# M7672X.net
KiCad netlist of a schematic drawn in EAGLE
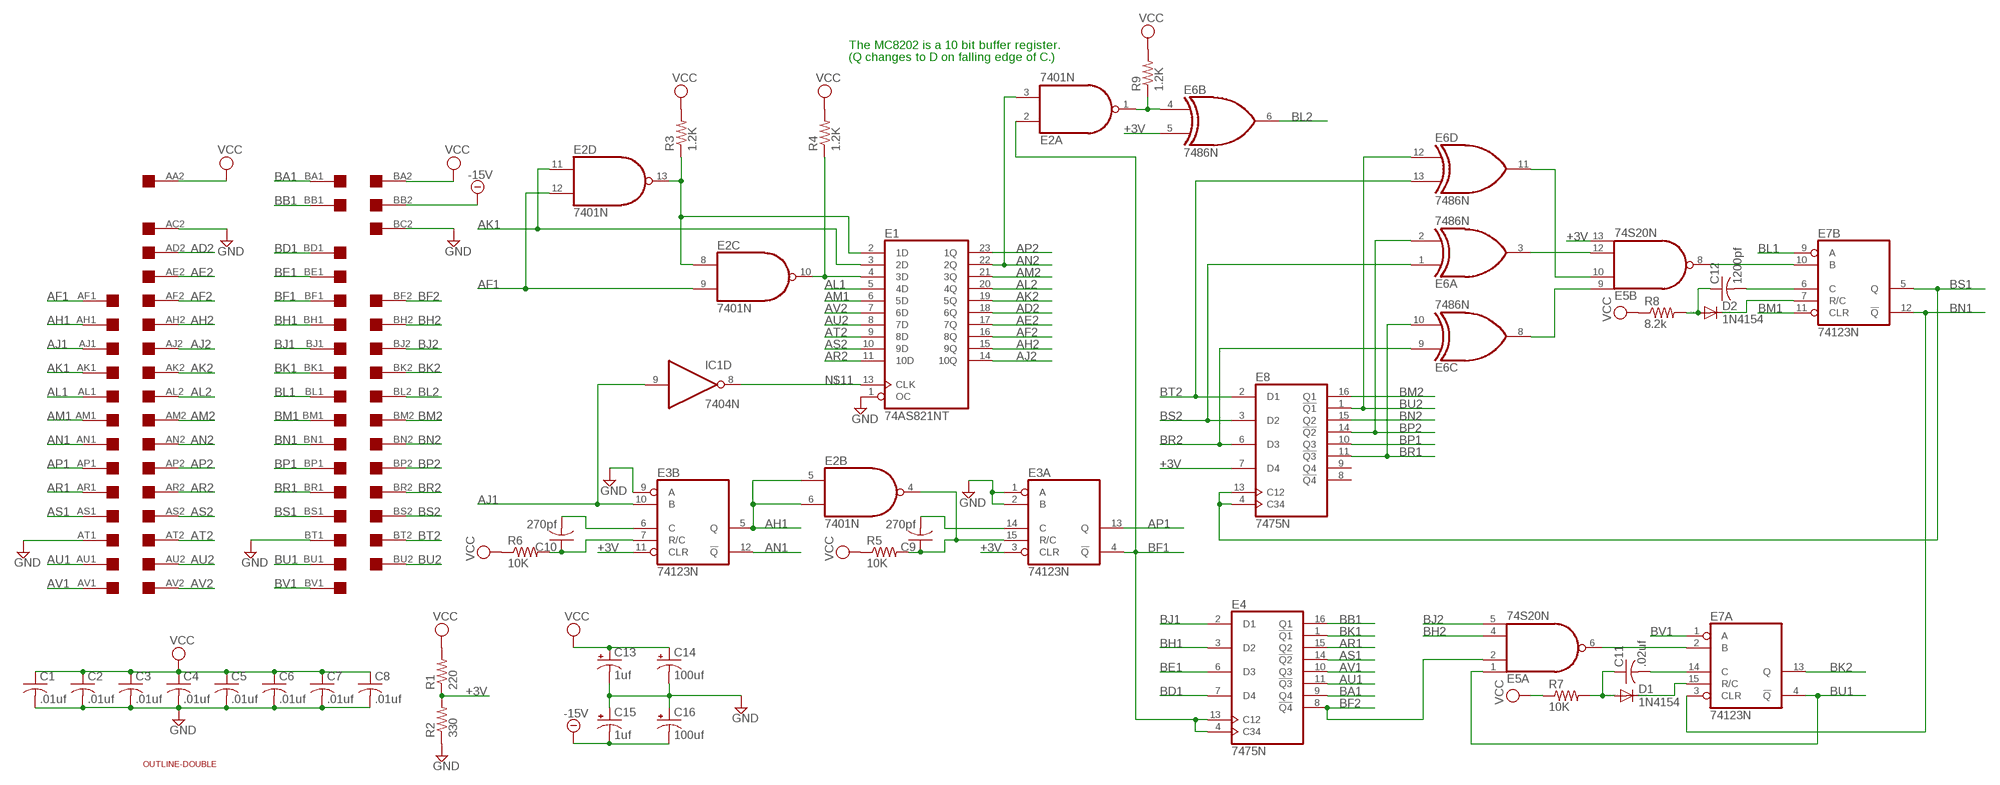
[diagram p0: schematic, sheet 1]

(export (version "E")
  (design (tool "Eeschema 10.0.6"))
  (components
    (comp (ref "C1")
      (value ".01uf")
      (footprint "eagle-import:C050-025X075")
      (libsource (lib "eagle-import") (part "C-US050-025X075"))
    )
    (comp (ref "C2")
      (value ".01uf")
      (footprint "eagle-import:C050-025X075")
      (libsource (lib "eagle-import") (part "C-US050-025X075"))
    )
    (comp (ref "C3")
      (value ".01uf")
      (footprint "eagle-import:C050-025X075")
      (libsource (lib "eagle-import") (part "C-US050-025X075"))
    )
    (comp (ref "C4")
      (value ".01uf")
      (footprint "eagle-import:C050-025X075")
      (libsource (lib "eagle-import") (part "C-US050-025X075"))
    )
    (comp (ref "C5")
      (value ".01uf")
      (footprint "eagle-import:C050-025X075")
      (libsource (lib "eagle-import") (part "C-US050-025X075"))
    )
    (comp (ref "C6")
      (value ".01uf")
      (footprint "eagle-import:C050-025X075")
      (libsource (lib "eagle-import") (part "C-US050-025X075"))
    )
    (comp (ref "C7")
      (value ".01uf")
      (footprint "eagle-import:C050-025X075")
      (libsource (lib "eagle-import") (part "C-US050-025X075"))
    )
    (comp (ref "C8")
      (value ".01uf")
      (footprint "eagle-import:C050-025X075")
      (libsource (lib "eagle-import") (part "C-US050-025X075"))
    )
    (comp (ref "C9")
      (value "270pf")
      (footprint "eagle-import:C050-025X075")
      (libsource (lib "eagle-import") (part "C-US050-025X075"))
    )
    (comp (ref "C10")
      (value "270pf")
      (footprint "eagle-import:C050-025X075")
      (libsource (lib "eagle-import") (part "C-US050-025X075"))
    )
    (comp (ref "C11")
      (value ".02uf")
      (footprint "eagle-import:C050-025X075")
      (libsource (lib "eagle-import") (part "C-US050-025X075"))
    )
    (comp (ref "C12")
      (value "1200pf")
      (footprint "eagle-import:C050-025X075")
      (libsource (lib "eagle-import") (part "C-US050-025X075"))
    )
    (comp (ref "C13")
      (value "1uf")
      (footprint "eagle-import:E30-10")
      (libsource (lib "eagle-import") (part "CPOL-USE30-10AXIAL"))
    )
    (comp (ref "C14")
      (value "100uf")
      (footprint "eagle-import:E30-10")
      (libsource (lib "eagle-import") (part "CPOL-USE30-10AXIAL"))
    )
    (comp (ref "C15")
      (value "1uf")
      (footprint "eagle-import:E30-10")
      (libsource (lib "eagle-import") (part "CPOL-USE30-10AXIAL"))
    )
    (comp (ref "C16")
      (value "100uf")
      (footprint "eagle-import:E30-10")
      (libsource (lib "eagle-import") (part "CPOL-USE30-10AXIAL"))
    )
    (comp (ref "D1")
      (value "1N4154")
      (footprint "eagle-import:DO35-10")
      (libsource (lib "eagle-import") (part "1N4148DO35-10"))
    )
    (comp (ref "D2")
      (value "1N4154")
      (footprint "eagle-import:DO35-10")
      (libsource (lib "eagle-import") (part "1N4148DO35-10"))
    )
    (comp (ref "E1")
      (value "74AS821NT")
      (footprint "eagle-import:DIL24-6")
      (libsource (lib "eagle-import") (part "74821NTAS"))
    )
    (comp (ref "E2")
      (value "7401N")
      (footprint "eagle-import:DIL14")
      (libsource (lib "eagle-import") (part "7401NLS"))
    )
    (comp (ref "E3")
      (value "74123N")
      (footprint "eagle-import:DIL16")
      (libsource (lib "eagle-import") (part "74123N"))
    )
    (comp (ref "E4")
      (value "7475N")
      (footprint "eagle-import:DIL16")
      (libsource (lib "eagle-import") (part "7475N"))
    )
    (comp (ref "E5")
      (value "74S20N")
      (footprint "eagle-import:DIL14")
      (libsource (lib "eagle-import") (part "7420NS"))
    )
    (comp (ref "E6")
      (value "7486N")
      (footprint "eagle-import:DIL14")
      (libsource (lib "eagle-import") (part "7486N"))
    )
    (comp (ref "E7")
      (value "74123N")
      (footprint "eagle-import:DIL16")
      (libsource (lib "eagle-import") (part "74123N"))
    )
    (comp (ref "E8")
      (value "7475N")
      (footprint "eagle-import:DIL16")
      (libsource (lib "eagle-import") (part "7475N"))
    )
    (comp (ref "EDGE")
      (value "DOUBLE")
      (footprint "eagle-import:EDGE-CON4")
      (libsource (lib "eagle-import") (part "DOUBLE"))
    )
    (comp (ref "IC1")
      (value "7404N")
      (footprint "eagle-import:DIL14")
      (libsource (lib "eagle-import") (part "7404N"))
    )
    (comp (ref "R1")
      (value "220")
      (footprint "eagle-import:0207_10")
      (libsource (lib "eagle-import") (part "R-US_0207/10"))
    )
    (comp (ref "R2")
      (value "330")
      (footprint "eagle-import:0207_10")
      (libsource (lib "eagle-import") (part "R-US_0207/10"))
    )
    (comp (ref "R3")
      (value "1.2K")
      (footprint "eagle-import:0207_10")
      (libsource (lib "eagle-import") (part "R-US_0207/10"))
    )
    (comp (ref "R4")
      (value "1.2K")
      (footprint "eagle-import:0207_10")
      (libsource (lib "eagle-import") (part "R-US_0207/10"))
    )
    (comp (ref "R5")
      (value "10K")
      (footprint "eagle-import:0207_10")
      (libsource (lib "eagle-import") (part "R-US_0207/10"))
    )
    (comp (ref "R6")
      (value "10K")
      (footprint "eagle-import:0207_10")
      (libsource (lib "eagle-import") (part "R-US_0207/10"))
    )
    (comp (ref "R7")
      (value "10K")
      (footprint "eagle-import:0207_10")
      (libsource (lib "eagle-import") (part "R-US_0207/10"))
    )
    (comp (ref "R8")
      (value "8.2k")
      (footprint "eagle-import:0207_10")
      (libsource (lib "eagle-import") (part "R-US_0207/10"))
    )
    (comp (ref "R9")
      (value "1.2K")
      (footprint "eagle-import:0207_10")
      (libsource (lib "eagle-import") (part "R-US_0207/10"))
    )
    (comp (ref "U$2")
      (value "OUTLINE-DOUBLE")
      (footprint "eagle-import:DOUBLE")
      (libsource (lib "eagle-import") (part "OUTLINE-DOUBLE"))
    )
  )
  (nets
    (net (code "1") (name "-15V") (class "Default")
      (node (ref "C15") (pin "-") (pinfunction "-_-") (pintype "passive"))
      (node (ref "C16") (pin "-") (pinfunction "-_-") (pintype "passive"))
      (node (ref "EDGE") (pin "BB2") (pinfunction "1_BB2") (pintype "bidirectional"))
    )
    (net (code "2") (name "/+3V") (class "Default")
      (node (ref "E3") (pin "11") (pinfunction "CLR_11") (pintype "input"))
      (node (ref "E3") (pin "3") (pinfunction "CLR_3") (pintype "input"))
      (node (ref "E5") (pin "13") (pinfunction "I3_13") (pintype "input"))
      (node (ref "E6") (pin "5") (pinfunction "I1_5") (pintype "input"))
      (node (ref "E8") (pin "7") (pinfunction "D4_7") (pintype "input"))
      (node (ref "R1") (pin "1") (pinfunction "1_1") (pintype "passive"))
      (node (ref "R2") (pin "2") (pinfunction "2_2") (pintype "passive"))
    )
    (net (code "3") (name "/AD2") (class "Default")
      (node (ref "E1") (pin "18") (pinfunction "6Q_18") (pintype "tri_state"))
      (node (ref "EDGE") (pin "AD2") (pinfunction "1_AD2") (pintype "bidirectional"))
    )
    (net (code "4") (name "/AE2") (class "Default")
      (node (ref "E1") (pin "17") (pinfunction "7Q_17") (pintype "tri_state"))
      (node (ref "EDGE") (pin "AE2") (pinfunction "1_AE2") (pintype "bidirectional"))
    )
    (net (code "5") (name "/AF1") (class "Default")
      (node (ref "E2") (pin "12") (pinfunction "I1_12") (pintype "input"))
      (node (ref "E2") (pin "9") (pinfunction "I1_9") (pintype "input"))
      (node (ref "EDGE") (pin "AF1") (pinfunction "1_AF1") (pintype "bidirectional"))
    )
    (net (code "6") (name "/AF2") (class "Default")
      (node (ref "E1") (pin "16") (pinfunction "8Q_16") (pintype "tri_state"))
      (node (ref "EDGE") (pin "AF2") (pinfunction "1_AF2") (pintype "bidirectional"))
    )
    (net (code "7") (name "/AH1") (class "Default")
      (node (ref "E2") (pin "5") (pinfunction "I0_5") (pintype "input"))
      (node (ref "E2") (pin "6") (pinfunction "I1_6") (pintype "input"))
      (node (ref "E3") (pin "5") (pinfunction "Q_5") (pintype "output"))
      (node (ref "EDGE") (pin "AH1") (pinfunction "1_AH1") (pintype "bidirectional"))
    )
    (net (code "8") (name "/AH2") (class "Default")
      (node (ref "E1") (pin "15") (pinfunction "9Q_15") (pintype "tri_state"))
      (node (ref "EDGE") (pin "AH2") (pinfunction "1_AH2") (pintype "bidirectional"))
    )
    (net (code "9") (name "/AJ1") (class "Default")
      (node (ref "E3") (pin "10") (pinfunction "B_10") (pintype "input"))
      (node (ref "EDGE") (pin "AJ1") (pinfunction "1_AJ1") (pintype "bidirectional"))
      (node (ref "IC1") (pin "9") (pinfunction "I_9") (pintype "input"))
    )
    (net (code "10") (name "/AJ2") (class "Default")
      (node (ref "E1") (pin "14") (pinfunction "10Q_14") (pintype "tri_state"))
      (node (ref "EDGE") (pin "AJ2") (pinfunction "1_AJ2") (pintype "bidirectional"))
    )
    (net (code "11") (name "/AK1") (class "Default")
      (node (ref "E1") (pin "3") (pinfunction "2D_3") (pintype "input"))
      (node (ref "E2") (pin "11") (pinfunction "I0_11") (pintype "input"))
      (node (ref "EDGE") (pin "AK1") (pinfunction "1_AK1") (pintype "bidirectional"))
    )
    (net (code "12") (name "/AK2") (class "Default")
      (node (ref "E1") (pin "19") (pinfunction "5Q_19") (pintype "tri_state"))
      (node (ref "EDGE") (pin "AK2") (pinfunction "1_AK2") (pintype "bidirectional"))
    )
    (net (code "13") (name "/AL1") (class "Default")
      (node (ref "E1") (pin "5") (pinfunction "4D_5") (pintype "input"))
      (node (ref "EDGE") (pin "AL1") (pinfunction "1_AL1") (pintype "bidirectional"))
    )
    (net (code "14") (name "/AL2") (class "Default")
      (node (ref "E1") (pin "20") (pinfunction "4Q_20") (pintype "tri_state"))
      (node (ref "EDGE") (pin "AL2") (pinfunction "1_AL2") (pintype "bidirectional"))
    )
    (net (code "15") (name "/AM1") (class "Default")
      (node (ref "E1") (pin "6") (pinfunction "5D_6") (pintype "input"))
      (node (ref "EDGE") (pin "AM1") (pinfunction "1_AM1") (pintype "bidirectional"))
    )
    (net (code "16") (name "/AM2") (class "Default")
      (node (ref "E1") (pin "21") (pinfunction "3Q_21") (pintype "tri_state"))
      (node (ref "EDGE") (pin "AM2") (pinfunction "1_AM2") (pintype "bidirectional"))
    )
    (net (code "17") (name "/AN1") (class "Default")
      (node (ref "E3") (pin "12") (pinfunction "~{Q}_12") (pintype "output"))
      (node (ref "EDGE") (pin "AN1") (pinfunction "1_AN1") (pintype "bidirectional"))
    )
    (net (code "18") (name "/AN2") (class "Default")
      (node (ref "E1") (pin "22") (pinfunction "2Q_22") (pintype "tri_state"))
      (node (ref "E2") (pin "3") (pinfunction "I1_3") (pintype "input"))
      (node (ref "EDGE") (pin "AN2") (pinfunction "1_AN2") (pintype "bidirectional"))
    )
    (net (code "19") (name "/AP1") (class "Default")
      (node (ref "E3") (pin "13") (pinfunction "Q_13") (pintype "output"))
      (node (ref "EDGE") (pin "AP1") (pinfunction "1_AP1") (pintype "bidirectional"))
    )
    (net (code "20") (name "/AP2") (class "Default")
      (node (ref "E1") (pin "23") (pinfunction "1Q_23") (pintype "tri_state"))
      (node (ref "EDGE") (pin "AP2") (pinfunction "1_AP2") (pintype "bidirectional"))
    )
    (net (code "21") (name "/AR1") (class "Default")
      (node (ref "E4") (pin "15") (pinfunction "Q2_15") (pintype "output"))
      (node (ref "EDGE") (pin "AR1") (pinfunction "1_AR1") (pintype "bidirectional"))
    )
    (net (code "22") (name "/AR2") (class "Default")
      (node (ref "E1") (pin "11") (pinfunction "10D_11") (pintype "input"))
      (node (ref "EDGE") (pin "AR2") (pinfunction "1_AR2") (pintype "bidirectional"))
    )
    (net (code "23") (name "/AS1") (class "Default")
      (node (ref "E4") (pin "14") (pinfunction "~{Q2}_14") (pintype "output"))
      (node (ref "EDGE") (pin "AS1") (pinfunction "1_AS1") (pintype "bidirectional"))
    )
    (net (code "24") (name "/AS2") (class "Default")
      (node (ref "E1") (pin "10") (pinfunction "9D_10") (pintype "input"))
      (node (ref "EDGE") (pin "AS2") (pinfunction "1_AS2") (pintype "bidirectional"))
    )
    (net (code "25") (name "/AT2") (class "Default")
      (node (ref "E1") (pin "9") (pinfunction "8D_9") (pintype "input"))
      (node (ref "EDGE") (pin "AT2") (pinfunction "1_AT2") (pintype "bidirectional"))
    )
    (net (code "26") (name "/AU1") (class "Default")
      (node (ref "E4") (pin "11") (pinfunction "~{Q3}_11") (pintype "output"))
      (node (ref "EDGE") (pin "AU1") (pinfunction "1_AU1") (pintype "bidirectional"))
    )
    (net (code "27") (name "/AU2") (class "Default")
      (node (ref "E1") (pin "8") (pinfunction "7D_8") (pintype "input"))
      (node (ref "EDGE") (pin "AU2") (pinfunction "1_AU2") (pintype "bidirectional"))
    )
    (net (code "28") (name "/AV1") (class "Default")
      (node (ref "E4") (pin "10") (pinfunction "Q3_10") (pintype "output"))
      (node (ref "EDGE") (pin "AV1") (pinfunction "1_AV1") (pintype "bidirectional"))
    )
    (net (code "29") (name "/AV2") (class "Default")
      (node (ref "E1") (pin "7") (pinfunction "6D_7") (pintype "input"))
      (node (ref "EDGE") (pin "AV2") (pinfunction "1_AV2") (pintype "bidirectional"))
    )
    (net (code "30") (name "/BA1") (class "Default")
      (node (ref "E4") (pin "9") (pinfunction "Q4_9") (pintype "output"))
      (node (ref "EDGE") (pin "BA1") (pinfunction "1_BA1") (pintype "bidirectional"))
    )
    (net (code "31") (name "/BB1") (class "Default")
      (node (ref "E4") (pin "16") (pinfunction "Q1_16") (pintype "output"))
      (node (ref "EDGE") (pin "BB1") (pinfunction "1_BB1") (pintype "bidirectional"))
    )
    (net (code "32") (name "/BD1") (class "Default")
      (node (ref "E4") (pin "7") (pinfunction "D4_7") (pintype "input"))
      (node (ref "EDGE") (pin "BD1") (pinfunction "1_BD1") (pintype "bidirectional"))
    )
    (net (code "33") (name "/BE1") (class "Default")
      (node (ref "E4") (pin "6") (pinfunction "D3_6") (pintype "input"))
      (node (ref "EDGE") (pin "BE1") (pinfunction "1_BE1") (pintype "bidirectional"))
    )
    (net (code "34") (name "/BF1") (class "Default")
      (node (ref "E2") (pin "2") (pinfunction "I0_2") (pintype "input"))
      (node (ref "E3") (pin "4") (pinfunction "~{Q}_4") (pintype "output"))
      (node (ref "E4") (pin "13") (pinfunction "C12_13") (pintype "input"))
      (node (ref "E4") (pin "4") (pinfunction "C34_4") (pintype "input"))
      (node (ref "EDGE") (pin "BF1") (pinfunction "1_BF1") (pintype "bidirectional"))
    )
    (net (code "35") (name "/BF2") (class "Default")
      (node (ref "E4") (pin "8") (pinfunction "~{Q4}_8") (pintype "output"))
      (node (ref "E5") (pin "2") (pinfunction "I1_2") (pintype "input"))
      (node (ref "EDGE") (pin "BF2") (pinfunction "1_BF2") (pintype "bidirectional"))
    )
    (net (code "36") (name "/BH1") (class "Default")
      (node (ref "E4") (pin "3") (pinfunction "D2_3") (pintype "input"))
      (node (ref "EDGE") (pin "BH1") (pinfunction "1_BH1") (pintype "bidirectional"))
    )
    (net (code "37") (name "/BH2") (class "Default")
      (node (ref "E5") (pin "4") (pinfunction "I2_4") (pintype "input"))
      (node (ref "EDGE") (pin "BH2") (pinfunction "1_BH2") (pintype "bidirectional"))
    )
    (net (code "38") (name "/BJ1") (class "Default")
      (node (ref "E4") (pin "2") (pinfunction "D1_2") (pintype "input"))
      (node (ref "EDGE") (pin "BJ1") (pinfunction "1_BJ1") (pintype "bidirectional"))
    )
    (net (code "39") (name "/BJ2") (class "Default")
      (node (ref "E5") (pin "5") (pinfunction "I3_5") (pintype "input"))
      (node (ref "EDGE") (pin "BJ2") (pinfunction "1_BJ2") (pintype "bidirectional"))
    )
    (net (code "40") (name "/BK1") (class "Default")
      (node (ref "E4") (pin "1") (pinfunction "~{Q1}_1") (pintype "output"))
      (node (ref "EDGE") (pin "BK1") (pinfunction "1_BK1") (pintype "bidirectional"))
    )
    (net (code "41") (name "/BK2") (class "Default")
      (node (ref "E7") (pin "13") (pinfunction "Q_13") (pintype "output"))
      (node (ref "EDGE") (pin "BK2") (pinfunction "1_BK2") (pintype "bidirectional"))
    )
    (net (code "42") (name "/BL1") (class "Default")
      (node (ref "E7") (pin "9") (pinfunction "A_9") (pintype "input"))
      (node (ref "EDGE") (pin "BL1") (pinfunction "1_BL1") (pintype "bidirectional"))
    )
    (net (code "43") (name "/BL2") (class "Default")
      (node (ref "E6") (pin "6") (pinfunction "O_6") (pintype "output"))
      (node (ref "EDGE") (pin "BL2") (pinfunction "1_BL2") (pintype "bidirectional"))
    )
    (net (code "44") (name "/BM1") (class "Default")
      (node (ref "E7") (pin "11") (pinfunction "CLR_11") (pintype "input"))
      (node (ref "EDGE") (pin "BM1") (pinfunction "1_BM1") (pintype "bidirectional"))
    )
    (net (code "45") (name "/BM2") (class "Default")
      (node (ref "E8") (pin "16") (pinfunction "Q1_16") (pintype "output"))
      (node (ref "EDGE") (pin "BM2") (pinfunction "1_BM2") (pintype "bidirectional"))
    )
    (net (code "46") (name "/BN1") (class "Default")
      (node (ref "E7") (pin "12") (pinfunction "~{Q}_12") (pintype "output"))
      (node (ref "E7") (pin "3") (pinfunction "CLR_3") (pintype "input"))
      (node (ref "EDGE") (pin "BN1") (pinfunction "1_BN1") (pintype "bidirectional"))
    )
    (net (code "47") (name "/BN2") (class "Default")
      (node (ref "E8") (pin "15") (pinfunction "Q2_15") (pintype "output"))
      (node (ref "EDGE") (pin "BN2") (pinfunction "1_BN2") (pintype "bidirectional"))
    )
    (net (code "48") (name "/BP1") (class "Default")
      (node (ref "E8") (pin "10") (pinfunction "Q3_10") (pintype "output"))
      (node (ref "EDGE") (pin "BP1") (pinfunction "1_BP1") (pintype "bidirectional"))
    )
    (net (code "49") (name "/BP2") (class "Default")
      (node (ref "E6") (pin "2") (pinfunction "I1_2") (pintype "input"))
      (node (ref "E8") (pin "14") (pinfunction "~{Q2}_14") (pintype "output"))
      (node (ref "EDGE") (pin "BP2") (pinfunction "1_BP2") (pintype "bidirectional"))
    )
    (net (code "50") (name "/BR1") (class "Default")
      (node (ref "E6") (pin "10") (pinfunction "I1_10") (pintype "input"))
      (node (ref "E8") (pin "11") (pinfunction "~{Q3}_11") (pintype "output"))
      (node (ref "EDGE") (pin "BR1") (pinfunction "1_BR1") (pintype "bidirectional"))
    )
    (net (code "51") (name "/BR2") (class "Default")
      (node (ref "E6") (pin "9") (pinfunction "I0_9") (pintype "input"))
      (node (ref "E8") (pin "6") (pinfunction "D3_6") (pintype "input"))
      (node (ref "EDGE") (pin "BR2") (pinfunction "1_BR2") (pintype "bidirectional"))
    )
    (net (code "52") (name "/BS1") (class "Default")
      (node (ref "E7") (pin "5") (pinfunction "Q_5") (pintype "output"))
      (node (ref "E8") (pin "13") (pinfunction "C12_13") (pintype "input"))
      (node (ref "E8") (pin "4") (pinfunction "C34_4") (pintype "input"))
      (node (ref "EDGE") (pin "BS1") (pinfunction "1_BS1") (pintype "bidirectional"))
    )
    (net (code "53") (name "/BS2") (class "Default")
      (node (ref "E6") (pin "1") (pinfunction "I0_1") (pintype "input"))
      (node (ref "E8") (pin "3") (pinfunction "D2_3") (pintype "input"))
      (node (ref "EDGE") (pin "BS2") (pinfunction "1_BS2") (pintype "bidirectional"))
    )
    (net (code "54") (name "/BT2") (class "Default")
      (node (ref "E6") (pin "13") (pinfunction "I1_13") (pintype "input"))
      (node (ref "E8") (pin "2") (pinfunction "D1_2") (pintype "input"))
      (node (ref "EDGE") (pin "BT2") (pinfunction "1_BT2") (pintype "bidirectional"))
    )
    (net (code "55") (name "/BU1") (class "Default")
      (node (ref "E5") (pin "1") (pinfunction "I0_1") (pintype "input"))
      (node (ref "E7") (pin "4") (pinfunction "~{Q}_4") (pintype "output"))
      (node (ref "EDGE") (pin "BU1") (pinfunction "1_BU1") (pintype "bidirectional"))
    )
    (net (code "56") (name "/BU2") (class "Default")
      (node (ref "E6") (pin "12") (pinfunction "I0_12") (pintype "input"))
      (node (ref "E8") (pin "1") (pinfunction "~{Q1}_1") (pintype "output"))
      (node (ref "EDGE") (pin "BU2") (pinfunction "1_BU2") (pintype "bidirectional"))
    )
    (net (code "57") (name "/BV1") (class "Default")
      (node (ref "E7") (pin "1") (pinfunction "A_1") (pintype "input"))
      (node (ref "EDGE") (pin "BV1") (pinfunction "1_BV1") (pintype "bidirectional"))
    )
    (net (code "58") (name "/N$11") (class "Default")
      (node (ref "E1") (pin "13") (pinfunction "CLK_13") (pintype "input"))
      (node (ref "IC1") (pin "8") (pinfunction "O_8") (pintype "output"))
    )
    (net (code "59") (name "GND") (class "Default")
      (node (ref "C1") (pin "2") (pinfunction "2_2") (pintype "passive"))
      (node (ref "C13") (pin "-") (pinfunction "-_-") (pintype "passive"))
      (node (ref "C14") (pin "-") (pinfunction "-_-") (pintype "passive"))
      (node (ref "C15") (pin "+") (pinfunction "+_+") (pintype "passive"))
      (node (ref "C16") (pin "+") (pinfunction "+_+") (pintype "passive"))
      (node (ref "C2") (pin "2") (pinfunction "2_2") (pintype "passive"))
      (node (ref "C3") (pin "2") (pinfunction "2_2") (pintype "passive"))
      (node (ref "C4") (pin "2") (pinfunction "2_2") (pintype "passive"))
      (node (ref "C5") (pin "2") (pinfunction "2_2") (pintype "passive"))
      (node (ref "C6") (pin "2") (pinfunction "2_2") (pintype "passive"))
      (node (ref "C7") (pin "2") (pinfunction "2_2") (pintype "passive"))
      (node (ref "C8") (pin "2") (pinfunction "2_2") (pintype "passive"))
      (node (ref "E1") (pin "1") (pinfunction "OC_1") (pintype "input"))
      (node (ref "E3") (pin "1") (pinfunction "A_1") (pintype "input"))
      (node (ref "E3") (pin "2") (pinfunction "B_2") (pintype "input"))
      (node (ref "E3") (pin "9") (pinfunction "A_9") (pintype "input"))
      (node (ref "EDGE") (pin "AC2") (pinfunction "1_AC2") (pintype "bidirectional"))
      (node (ref "EDGE") (pin "AT1") (pinfunction "1_AT1") (pintype "bidirectional"))
      (node (ref "EDGE") (pin "BC2") (pinfunction "1_BC2") (pintype "bidirectional"))
      (node (ref "EDGE") (pin "BT1") (pinfunction "1_BT1") (pintype "bidirectional"))
      (node (ref "R2") (pin "1") (pinfunction "1_1") (pintype "passive"))
    )
    (net (code "60") (name "Net-(C11-Pad1)") (class "Default")
      (node (ref "C11") (pin "1") (pinfunction "1_1") (pintype "passive"))
      (node (ref "D1") (pin "A") (pinfunction "A_A") (pintype "passive"))
      (node (ref "R7") (pin "2") (pinfunction "2_2") (pintype "passive"))
    )
    (net (code "61") (name "Net-(C12-Pad1)") (class "Default")
      (node (ref "C12") (pin "1") (pinfunction "1_1") (pintype "passive"))
      (node (ref "D2") (pin "A") (pinfunction "A_A") (pintype "passive"))
      (node (ref "R8") (pin "2") (pinfunction "2_2") (pintype "passive"))
    )
    (net (code "62") (name "Net-(E1A-1D)") (class "Default")
      (node (ref "E1") (pin "2") (pinfunction "1D_2") (pintype "input"))
      (node (ref "E2") (pin "13") (pinfunction "O_13") (pintype "open_collector"))
      (node (ref "E2") (pin "8") (pinfunction "I0_8") (pintype "input"))
      (node (ref "R3") (pin "1") (pinfunction "1_1") (pintype "passive"))
    )
    (net (code "63") (name "Net-(E1A-3D)") (class "Default")
      (node (ref "E1") (pin "4") (pinfunction "3D_4") (pintype "input"))
      (node (ref "E2") (pin "10") (pinfunction "O_10") (pintype "open_collector"))
      (node (ref "R4") (pin "1") (pinfunction "1_1") (pintype "passive"))
    )
    (net (code "64") (name "Net-(E2A-O)") (class "Default")
      (node (ref "E2") (pin "1") (pinfunction "O_1") (pintype "open_collector"))
      (node (ref "E6") (pin "4") (pinfunction "I0_4") (pintype "input"))
      (node (ref "R9") (pin "1") (pinfunction "1_1") (pintype "passive"))
    )
    (net (code "65") (name "Net-(E2B-O)") (class "Default")
      (node (ref "C9") (pin "1") (pinfunction "1_1") (pintype "passive"))
      (node (ref "E2") (pin "4") (pinfunction "O_4") (pintype "open_collector"))
      (node (ref "E3") (pin "15") (pinfunction "R/C_15") (pintype "input"))
      (node (ref "R5") (pin "2") (pinfunction "2_2") (pintype "passive"))
    )
    (net (code "66") (name "Net-(E3A-C)") (class "Default")
      (node (ref "C9") (pin "2") (pinfunction "2_2") (pintype "passive"))
      (node (ref "E3") (pin "14") (pinfunction "C_14") (pintype "input"))
    )
    (net (code "67") (name "Net-(E3B-C)") (class "Default")
      (node (ref "C10") (pin "2") (pinfunction "2_2") (pintype "passive"))
      (node (ref "E3") (pin "6") (pinfunction "C_6") (pintype "input"))
    )
    (net (code "68") (name "Net-(E3B-R{slash}C)") (class "Default")
      (node (ref "C10") (pin "1") (pinfunction "1_1") (pintype "passive"))
      (node (ref "E3") (pin "7") (pinfunction "R/C_7") (pintype "input"))
      (node (ref "R6") (pin "2") (pinfunction "2_2") (pintype "passive"))
    )
    (net (code "69") (name "Net-(E5A-O)") (class "Default")
      (node (ref "E5") (pin "6") (pinfunction "O_6") (pintype "output"))
      (node (ref "E7") (pin "2") (pinfunction "B_2") (pintype "input"))
    )
    (net (code "70") (name "Net-(E5B-I0)") (class "Default")
      (node (ref "E5") (pin "9") (pinfunction "I0_9") (pintype "input"))
      (node (ref "E6") (pin "8") (pinfunction "O_8") (pintype "output"))
    )
    (net (code "71") (name "Net-(E5B-I1)") (class "Default")
      (node (ref "E5") (pin "10") (pinfunction "I1_10") (pintype "input"))
      (node (ref "E6") (pin "11") (pinfunction "O_11") (pintype "output"))
    )
    (net (code "72") (name "Net-(E5B-I2)") (class "Default")
      (node (ref "E5") (pin "12") (pinfunction "I2_12") (pintype "input"))
      (node (ref "E6") (pin "3") (pinfunction "O_3") (pintype "output"))
    )
    (net (code "73") (name "Net-(E5B-O)") (class "Default")
      (node (ref "E5") (pin "8") (pinfunction "O_8") (pintype "output"))
      (node (ref "E7") (pin "10") (pinfunction "B_10") (pintype "input"))
    )
    (net (code "74") (name "Net-(E7A-C)") (class "Default")
      (node (ref "C11") (pin "2") (pinfunction "2_2") (pintype "passive"))
      (node (ref "E7") (pin "14") (pinfunction "C_14") (pintype "input"))
    )
    (net (code "75") (name "Net-(E7A-R{slash}C)") (class "Default")
      (node (ref "D1") (pin "C") (pinfunction "C_C") (pintype "passive"))
      (node (ref "E7") (pin "15") (pinfunction "R/C_15") (pintype "input"))
    )
    (net (code "76") (name "Net-(E7B-C)") (class "Default")
      (node (ref "C12") (pin "2") (pinfunction "2_2") (pintype "passive"))
      (node (ref "E7") (pin "6") (pinfunction "C_6") (pintype "input"))
    )
    (net (code "77") (name "Net-(E7B-R{slash}C)") (class "Default")
      (node (ref "D2") (pin "C") (pinfunction "C_C") (pintype "passive"))
      (node (ref "E7") (pin "7") (pinfunction "R/C_7") (pintype "input"))
    )
    (net (code "78") (name "VCC") (class "Default")
      (node (ref "C1") (pin "1") (pinfunction "1_1") (pintype "passive"))
      (node (ref "C13") (pin "+") (pinfunction "+_+") (pintype "passive"))
      (node (ref "C14") (pin "+") (pinfunction "+_+") (pintype "passive"))
      (node (ref "C2") (pin "1") (pinfunction "1_1") (pintype "passive"))
      (node (ref "C3") (pin "1") (pinfunction "1_1") (pintype "passive"))
      (node (ref "C4") (pin "1") (pinfunction "1_1") (pintype "passive"))
      (node (ref "C5") (pin "1") (pinfunction "1_1") (pintype "passive"))
      (node (ref "C6") (pin "1") (pinfunction "1_1") (pintype "passive"))
      (node (ref "C7") (pin "1") (pinfunction "1_1") (pintype "passive"))
      (node (ref "C8") (pin "1") (pinfunction "1_1") (pintype "passive"))
      (node (ref "EDGE") (pin "AA2") (pinfunction "1_AA2") (pintype "bidirectional"))
      (node (ref "EDGE") (pin "BA2") (pinfunction "1_BA2") (pintype "bidirectional"))
      (node (ref "R1") (pin "2") (pinfunction "2_2") (pintype "passive"))
      (node (ref "R3") (pin "2") (pinfunction "2_2") (pintype "passive"))
      (node (ref "R4") (pin "2") (pinfunction "2_2") (pintype "passive"))
      (node (ref "R5") (pin "1") (pinfunction "1_1") (pintype "passive"))
      (node (ref "R6") (pin "1") (pinfunction "1_1") (pintype "passive"))
      (node (ref "R7") (pin "1") (pinfunction "1_1") (pintype "passive"))
      (node (ref "R8") (pin "1") (pinfunction "1_1") (pintype "passive"))
      (node (ref "R9") (pin "2") (pinfunction "2_2") (pintype "passive"))
    )
    (net (code "79") (name "unconnected-(E8A-Q4-Pad9)") (class "Default")
      (node (ref "E8") (pin "9") (pinfunction "Q4_9") (pintype "output"))
    )
    (net (code "80") (name "unconnected-(E8A-~{Q4}-Pad8)") (class "Default")
      (node (ref "E8") (pin "8") (pinfunction "~{Q4}_8") (pintype "output"))
    )
  )
)
